# QSPI.net
KiCad netlist of a schematic drawn in Altium Designer
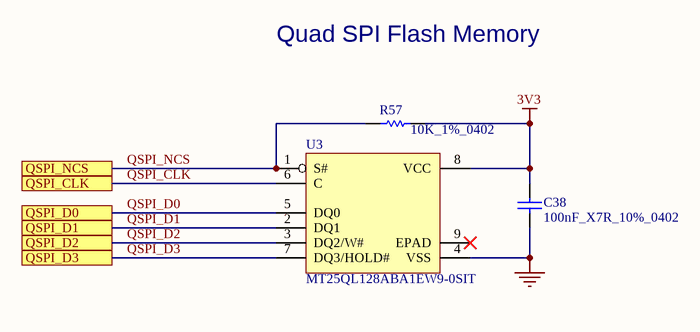
[diagram p0: QSPI.SchDoc]

(export (version "E")
  (design (tool "Eeschema 10.0.6"))
  (components
    (comp (ref "C38")
      (value "100nF_X7R_10%_0402")
      (footprint "0402C")
      (description "Capacitor,100nF,16V,X7R,10%,0402,YAGEO")
      (libsource (lib "MCD_TOOLS") (part "Cap_100nF_X7R_10%_0402"))
    )
    (comp (ref "R57")
      (value "10K_1%_0402")
      (footprint "0402R")
      (description "Resistor,10K,0402,1%,YAGEO")
      (libsource (lib "MCD_TOOLS") (part "Res_10K_1%_0402"))
    )
    (comp (ref "U3")
      (value "MT25QL128ABA1EW9-0SIT")
      (footprint "W-PDFN-8_8X6_P127")
      (description "128Mb, 3V, Multiple I/O Serial Flash Memory, Quad/Dual")
      (libsource (lib "Mb1191") (part "MT25QL128ABA1EW9-0SIT"))
    )
  )
  (nets
    (net (code "1") (name "/QSPI_CLK") (class "Default")
      (node (ref "U3") (pin "6") (pinfunction "C_6") (pintype "passive"))
    )
    (net (code "2") (name "/QSPI_D0") (class "Default")
      (node (ref "U3") (pin "5") (pinfunction "DQ0_5") (pintype "passive"))
    )
    (net (code "3") (name "/QSPI_D1") (class "Default")
      (node (ref "U3") (pin "2") (pinfunction "DQ1_2") (pintype "passive"))
    )
    (net (code "4") (name "/QSPI_D2") (class "Default")
      (node (ref "U3") (pin "3") (pinfunction "DQ2/W#_3") (pintype "passive"))
    )
    (net (code "5") (name "/QSPI_D3") (class "Default")
      (node (ref "U3") (pin "7") (pinfunction "DQ3/HOLD#_7") (pintype "passive"))
    )
    (net (code "6") (name "/QSPI_NCS") (class "Default")
      (node (ref "R57") (pin "1") (pinfunction "1_1") (pintype "passive"))
      (node (ref "U3") (pin "1") (pinfunction "S#_1") (pintype "passive"))
    )
    (net (code "7") (name "3V3") (class "Default")
      (node (ref "C38") (pin "2") (pinfunction "2_2") (pintype "passive"))
      (node (ref "R57") (pin "2") (pinfunction "2_2") (pintype "passive"))
      (node (ref "U3") (pin "8") (pinfunction "VCC_8") (pintype "passive"))
    )
    (net (code "8") (name "GND") (class "Default")
      (node (ref "C38") (pin "1") (pinfunction "1_1") (pintype "passive"))
      (node (ref "U3") (pin "4") (pinfunction "VSS_4") (pintype "passive"))
    )
    (net (code "9") (name "unconnected-(U3-EPAD-Pad9)") (class "Default")
      (node (ref "U3") (pin "9") (pinfunction "EPAD_9") (pintype "passive+no_connect"))
    )
  )
)
